# SCH_VoltageRegulator_2021-10-04.net
KiCad netlist of a schematic drawn in EasyEDA
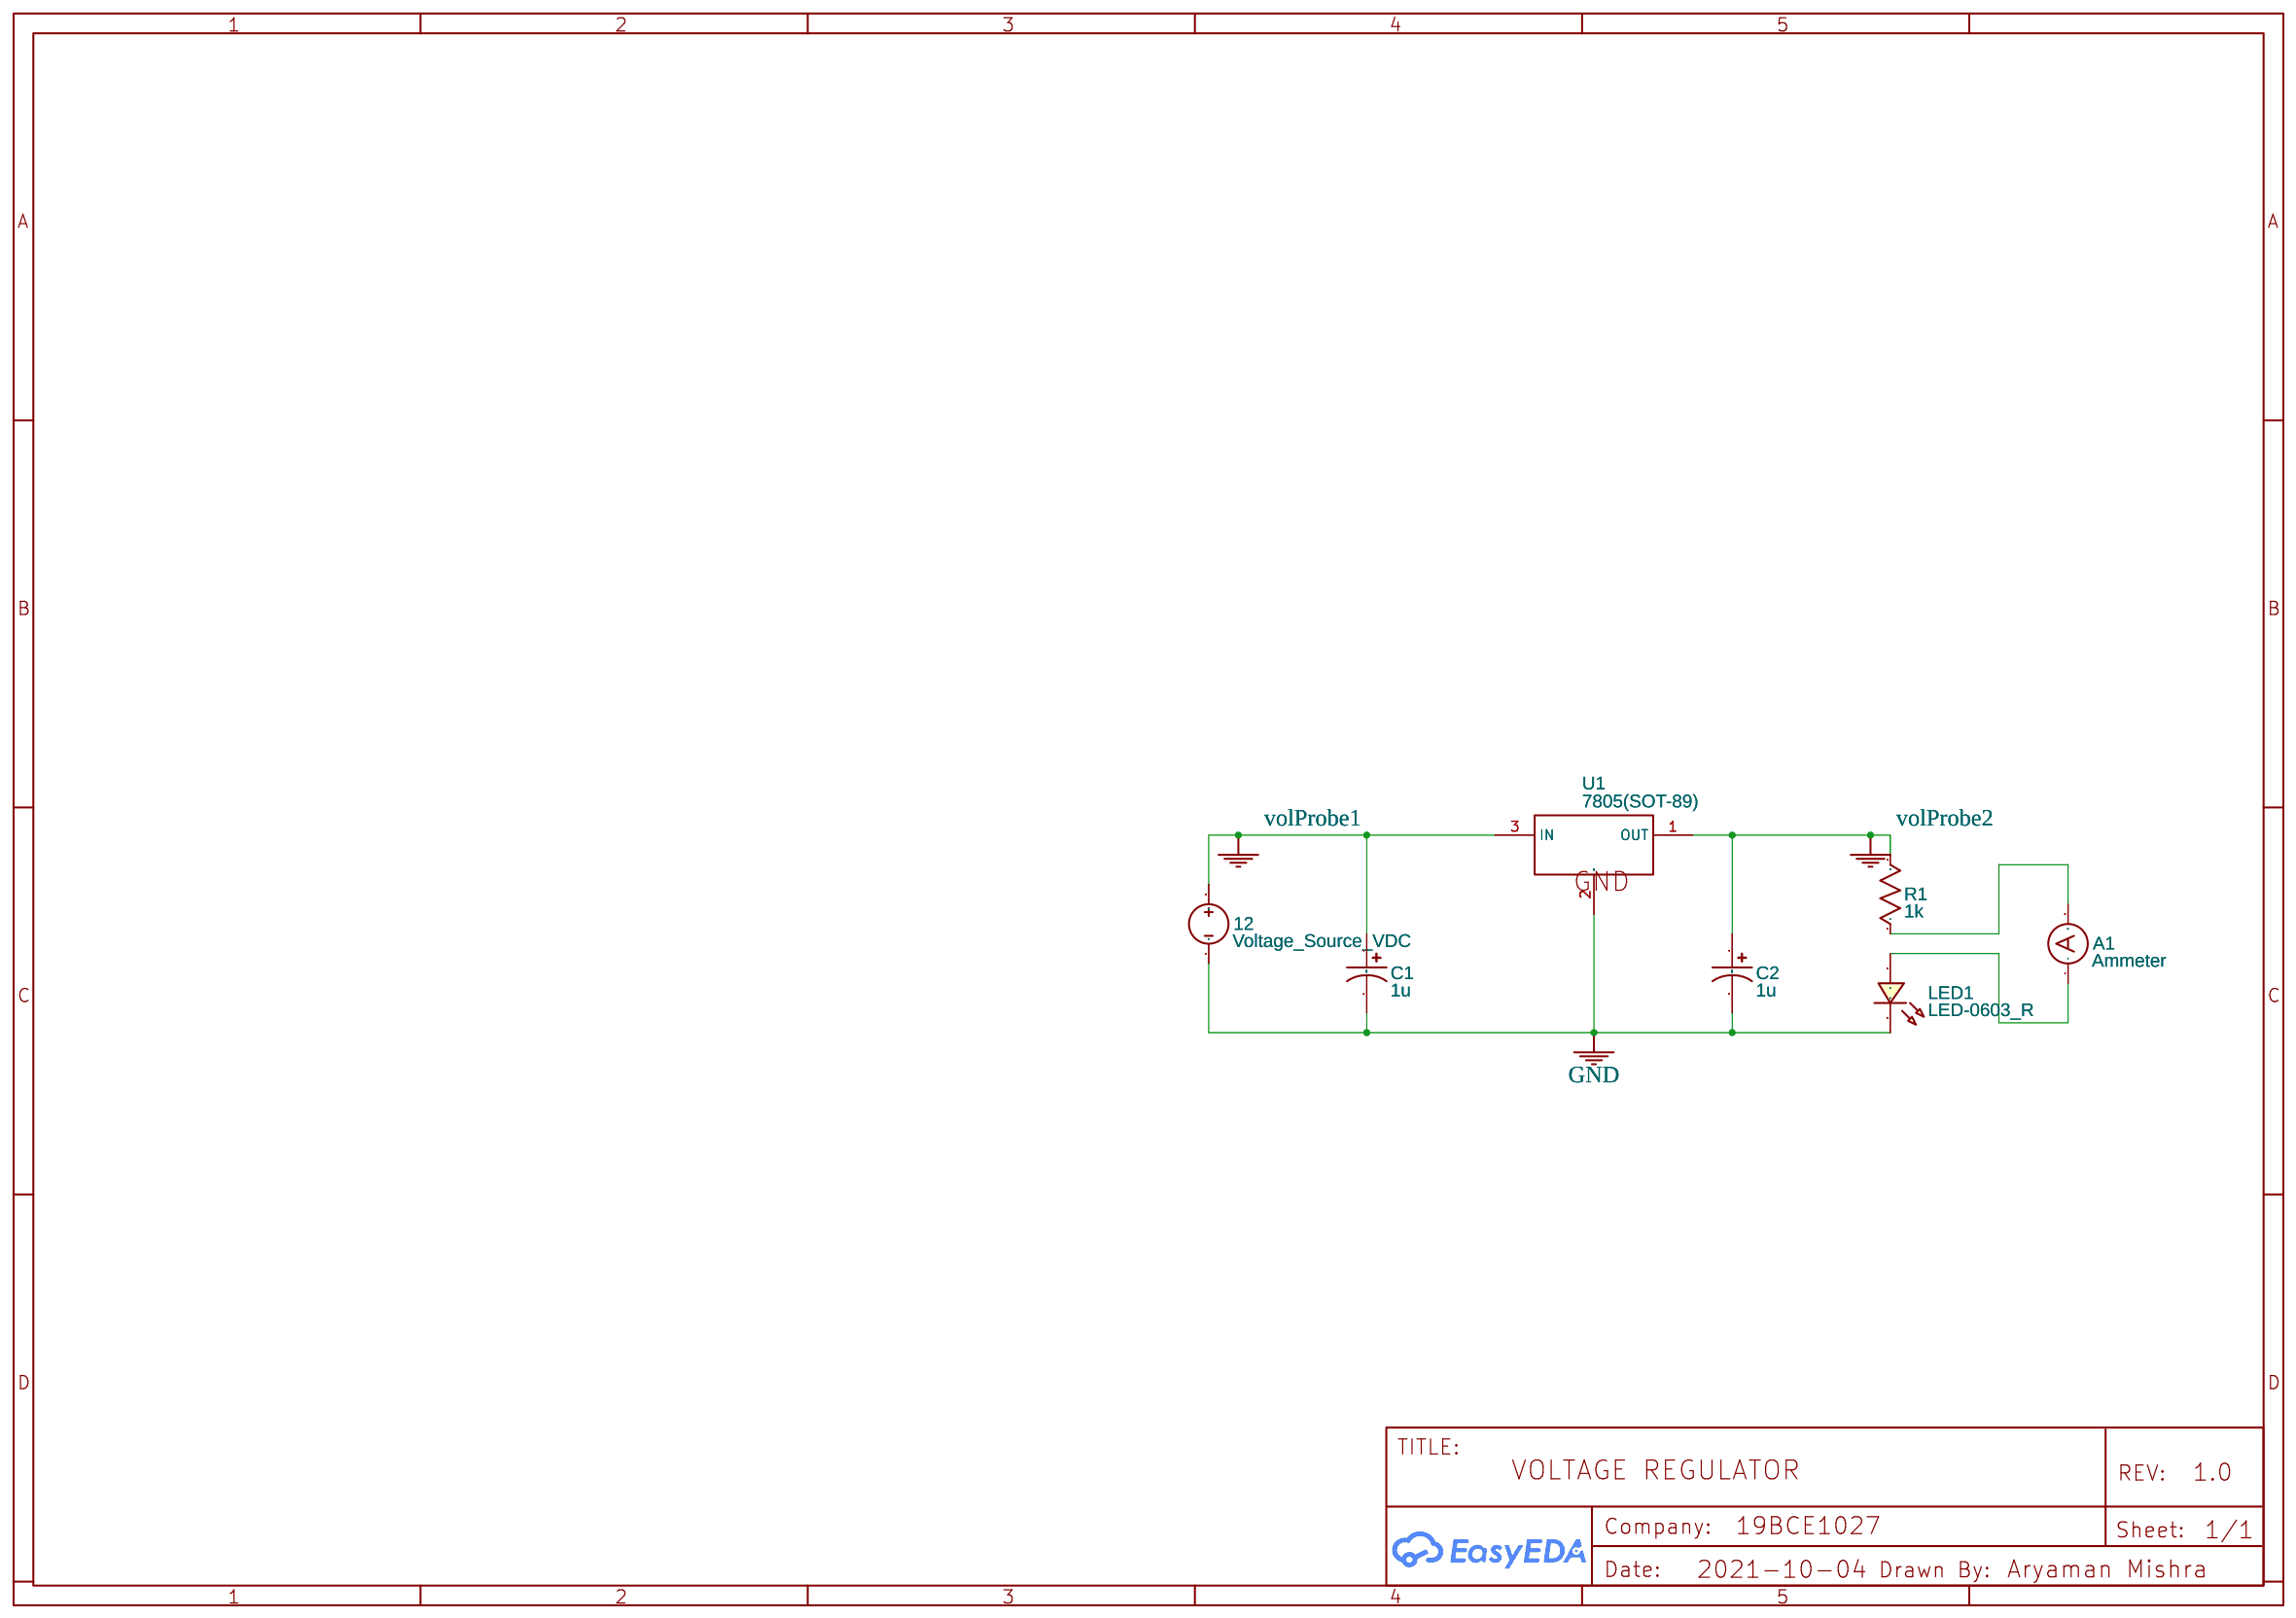
[diagram p0: schematic sheet]

(export (version "E")
  (design (tool "Eeschema 10.0.6"))
  (components
    (comp (ref "12") (value "Voltage_Source_VDC") (libsource (lib "") (part "VDC")))
    (comp (ref "A1") (value "Ammeter") (libsource (lib "") (part "Ammeter")))
    (comp (ref "C1") (value "1u") (libsource (lib "") (part "CE_SMD_D4.0×H5.5_US")))
    (comp (ref "C2") (value "1u") (libsource (lib "") (part "CE_SMD_D4.0×H5.5_US")))
    (comp (ref "LED1")
      (value "LED-0603_R")
      (fields
        (field (name "BOM_Manufacturer Part") "19-217/R6C-AL1M2VY/3T")
        (field (name "BOM_Supplier Part") "C72044")
      )
      (libsource (lib "") (part "LED-0603_R"))
    )
    (comp (ref "R1") (value "1k") (libsource (lib "") (part "R_0603_US")))
    (comp (ref "U1")
      (value "7805(SOT-89)")
      (fields (field (name "BOM_Manufacturer Part") "CJ78L05") (field (name "BOM_Supplier Part") "C2079"))
      (libsource (lib "") (part "7805(SOT-89)"))
    )
  )
  (nets
    (net (code "1") (name "GND") (class "Default")
      (node (ref "12") (pin "2") (pinfunction "2_2") (pintype "unspecified"))
      (node (ref "C1") (pin "2") (pinfunction "2_2") (pintype "unspecified"))
      (node (ref "C2") (pin "2") (pinfunction "2_2") (pintype "unspecified"))
      (node (ref "LED1") (pin "2") (pinfunction "2_2") (pintype "unspecified"))
      (node (ref "U1") (pin "2") (pinfunction "GND_2") (pintype "passive"))
    )
    (net (code "2") (name "Net-(A1-+)") (class "Default")
      (node (ref "A1") (pin "1") (pinfunction "+_1") (pintype "unspecified"))
      (node (ref "LED1") (pin "1") (pinfunction "1_1") (pintype "unspecified"))
    )
    (net (code "3") (name "Net-(A1-Pad2)") (class "Default")
      (node (ref "A1") (pin "2") (pinfunction "2_2") (pintype "unspecified"))
      (node (ref "R1") (pin "1") (pinfunction "1_1") (pintype "unspecified"))
    )
    (net (code "4") (name "volProbe1") (class "Default")
      (node (ref "12") (pin "1") (pinfunction "1_1") (pintype "unspecified"))
      (node (ref "C1") (pin "1") (pinfunction "1_1") (pintype "unspecified"))
      (node (ref "U1") (pin "3") (pinfunction "IN_3") (pintype "passive"))
    )
    (net (code "5") (name "volProbe2") (class "Default")
      (node (ref "C2") (pin "1") (pinfunction "1_1") (pintype "unspecified"))
      (node (ref "R1") (pin "2") (pinfunction "2_2") (pintype "unspecified"))
      (node (ref "U1") (pin "1") (pinfunction "OUT_1") (pintype "passive"))
    )
  )
)
